# analog.net
KiCad netlist of a schematic drawn in Altium Designer
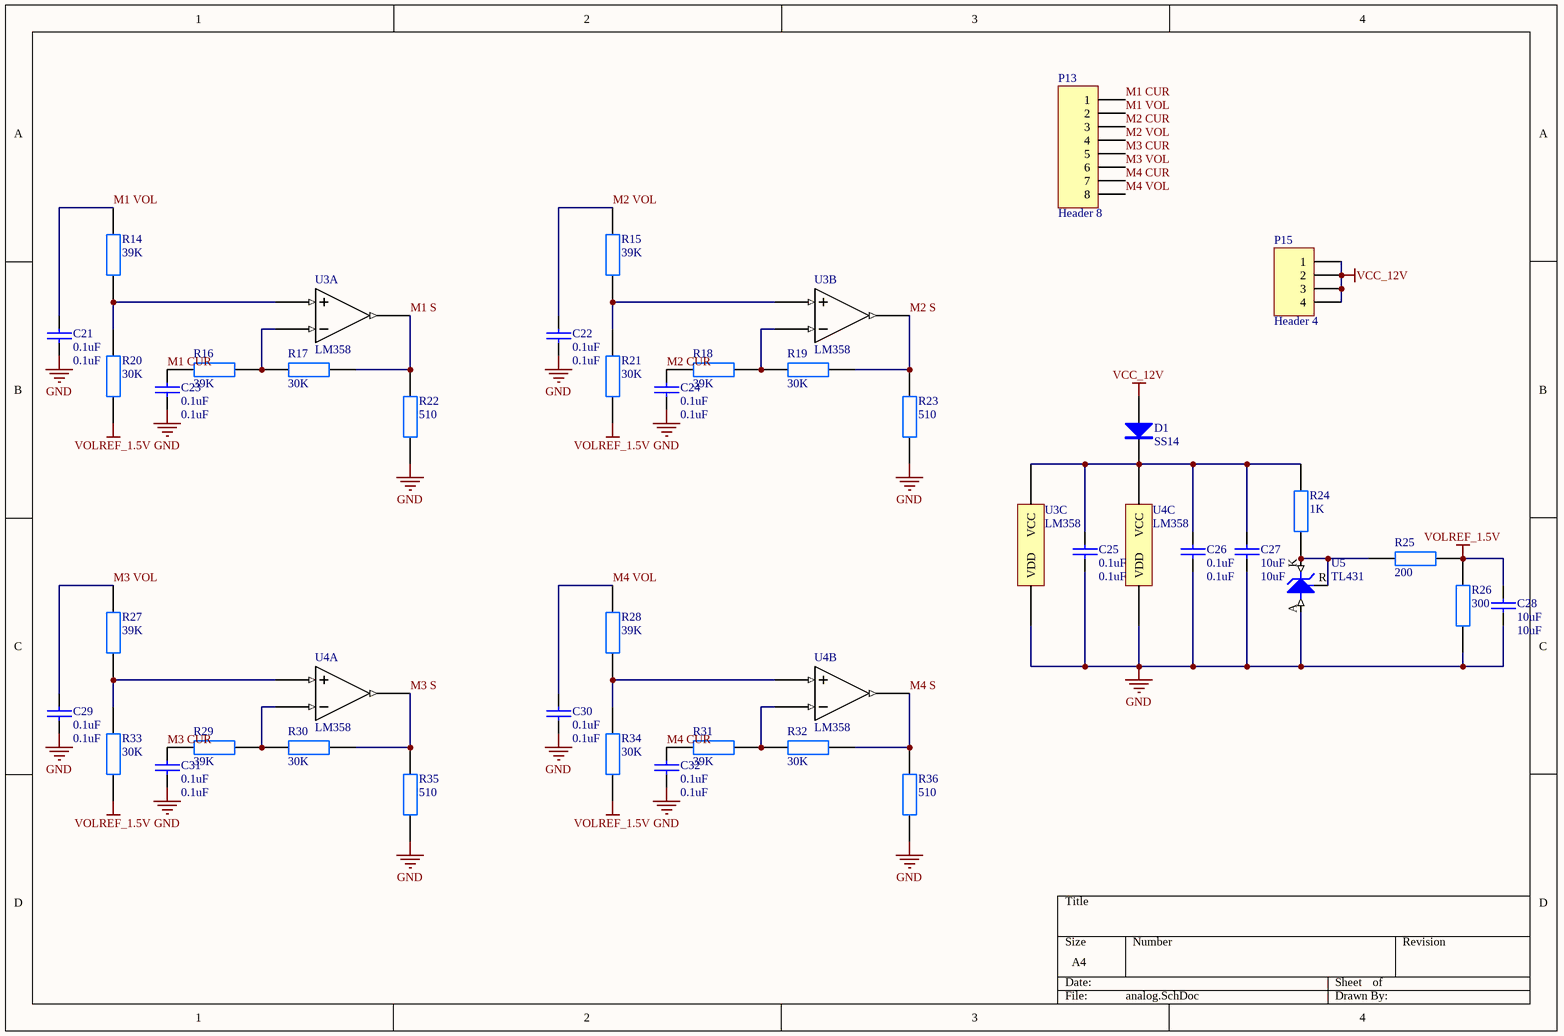
[diagram p0: analog.SchDoc]

(export (version "E")
  (design (tool "Eeschema 10.0.6"))
  (components
    (comp (ref "C21")
      (value "0.1uF")
      (footprint "0805 CAP")
      (fields (field (name "ALTIUM_VALUE") "0.1uF"))
      (libsource (lib "common") (part "CAP"))
    )
    (comp (ref "C22")
      (value "0.1uF")
      (footprint "0805 CAP")
      (fields (field (name "ALTIUM_VALUE") "0.1uF"))
      (libsource (lib "common") (part "CAP"))
    )
    (comp (ref "C23")
      (value "0.1uF")
      (footprint "0805 CAP")
      (fields (field (name "ALTIUM_VALUE") "0.1uF"))
      (libsource (lib "common") (part "CAP"))
    )
    (comp (ref "C24")
      (value "0.1uF")
      (footprint "0805 CAP")
      (fields (field (name "ALTIUM_VALUE") "0.1uF"))
      (libsource (lib "common") (part "CAP"))
    )
    (comp (ref "C25")
      (value "0.1uF")
      (footprint "0805 CAP")
      (fields (field (name "ALTIUM_VALUE") "0.1uF"))
      (libsource (lib "common") (part "CAP"))
    )
    (comp (ref "C26")
      (value "0.1uF")
      (footprint "0805 CAP")
      (fields (field (name "ALTIUM_VALUE") "0.1uF"))
      (libsource (lib "common") (part "CAP"))
    )
    (comp (ref "C27")
      (value "10uF")
      (footprint "0805 CAP")
      (fields (field (name "ALTIUM_VALUE") "10uF"))
      (libsource (lib "common") (part "CAP"))
    )
    (comp (ref "C28")
      (value "10uF")
      (footprint "0805 CAP")
      (fields (field (name "ALTIUM_VALUE") "10uF"))
      (libsource (lib "common") (part "CAP"))
    )
    (comp (ref "C29")
      (value "0.1uF")
      (footprint "0805 CAP")
      (fields (field (name "ALTIUM_VALUE") "0.1uF"))
      (libsource (lib "common") (part "CAP"))
    )
    (comp (ref "C30")
      (value "0.1uF")
      (footprint "0805 CAP")
      (fields (field (name "ALTIUM_VALUE") "0.1uF"))
      (libsource (lib "common") (part "CAP"))
    )
    (comp (ref "C31")
      (value "0.1uF")
      (footprint "0805 CAP")
      (fields (field (name "ALTIUM_VALUE") "0.1uF"))
      (libsource (lib "common") (part "CAP"))
    )
    (comp (ref "C32")
      (value "0.1uF")
      (footprint "0805 CAP")
      (fields (field (name "ALTIUM_VALUE") "0.1uF"))
      (libsource (lib "common") (part "CAP"))
    )
    (comp (ref "D1")
      (value "SS14")
      (footprint "DO-241AC")
      (description "Diode")
      (libsource (lib "common") (part "SS14"))
    )
    (comp (ref "P13")
      (value "Header 8")
      (footprint "sip8 i")
      (description "Header, 8-Pin")
      (fields (field (name "PUBLISHER") "Altium Limited"))
      (libsource (lib "Miscellaneous Connectors") (part "Header 8"))
    )
    (comp (ref "P15")
      (value "Header 4")
      (footprint "sip4 i")
      (description "Header, 4-Pin")
      (fields (field (name "PUBLISHER") "Altium Limited"))
      (libsource (lib "Miscellaneous Connectors") (part "Header 4"))
    )
    (comp (ref "R14")
      (value "39K")
      (footprint "0805")
      (description "RES")
      (libsource (lib "common") (part "RES"))
    )
    (comp (ref "R15")
      (value "39K")
      (footprint "0805")
      (description "RES")
      (libsource (lib "common") (part "RES"))
    )
    (comp (ref "R16")
      (value "39K")
      (footprint "0805")
      (description "RES")
      (libsource (lib "common") (part "RES"))
    )
    (comp (ref "R17")
      (value "30K")
      (footprint "0805")
      (description "RES")
      (libsource (lib "common") (part "RES"))
    )
    (comp (ref "R18")
      (value "39K")
      (footprint "0805")
      (description "RES")
      (libsource (lib "common") (part "RES"))
    )
    (comp (ref "R19")
      (value "30K")
      (footprint "0805")
      (description "RES")
      (libsource (lib "common") (part "RES"))
    )
    (comp (ref "R20")
      (value "30K")
      (footprint "0805")
      (description "RES")
      (libsource (lib "common") (part "RES"))
    )
    (comp (ref "R21")
      (value "30K")
      (footprint "0805")
      (description "RES")
      (libsource (lib "common") (part "RES"))
    )
    (comp (ref "R22")
      (value "510")
      (footprint "0805")
      (description "RES")
      (libsource (lib "common") (part "RES"))
    )
    (comp (ref "R23")
      (value "510")
      (footprint "0805")
      (description "RES")
      (libsource (lib "common") (part "RES"))
    )
    (comp (ref "R24")
      (value "1K")
      (footprint "0805")
      (description "RES")
      (libsource (lib "common") (part "RES"))
    )
    (comp (ref "R25")
      (value "200")
      (footprint "0805")
      (description "RES")
      (libsource (lib "common") (part "RES"))
    )
    (comp (ref "R26")
      (value "300")
      (footprint "0805")
      (description "RES")
      (libsource (lib "common") (part "RES"))
    )
    (comp (ref "R27")
      (value "39K")
      (footprint "0805")
      (description "RES")
      (libsource (lib "common") (part "RES"))
    )
    (comp (ref "R28")
      (value "39K")
      (footprint "0805")
      (description "RES")
      (libsource (lib "common") (part "RES"))
    )
    (comp (ref "R29")
      (value "39K")
      (footprint "0805")
      (description "RES")
      (libsource (lib "common") (part "RES"))
    )
    (comp (ref "R30")
      (value "30K")
      (footprint "0805")
      (description "RES")
      (libsource (lib "common") (part "RES"))
    )
    (comp (ref "R31")
      (value "39K")
      (footprint "0805")
      (description "RES")
      (libsource (lib "common") (part "RES"))
    )
    (comp (ref "R32")
      (value "30K")
      (footprint "0805")
      (description "RES")
      (libsource (lib "common") (part "RES"))
    )
    (comp (ref "R33")
      (value "30K")
      (footprint "0805")
      (description "RES")
      (libsource (lib "common") (part "RES"))
    )
    (comp (ref "R34")
      (value "30K")
      (footprint "0805")
      (description "RES")
      (libsource (lib "common") (part "RES"))
    )
    (comp (ref "R35")
      (value "510")
      (footprint "0805")
      (description "RES")
      (libsource (lib "common") (part "RES"))
    )
    (comp (ref "R36")
      (value "510")
      (footprint "0805")
      (description "RES")
      (libsource (lib "common") (part "RES"))
    )
    (comp (ref "U3") (value "LM358") (footprint "so-8") (libsource (lib "common") (part "LM358")))
    (comp (ref "U4") (value "LM358") (footprint "so-8") (libsource (lib "") (part "LM358_1")))
    (comp (ref "U5")
      (value "TL431")
      (footprint "sot-23")
      (description "IC")
      (libsource (lib "common") (part "TL431"))
    )
  )
  (nets
    (net (code "1") (name "/M1 CUR") (class "Default")
      (node (ref "C23") (pin "1") (pinfunction "1_1") (pintype "passive"))
      (node (ref "P13") (pin "1") (pinfunction "1_1") (pintype "passive"))
      (node (ref "R16") (pin "2") (pinfunction "2_2") (pintype "passive"))
    )
    (net (code "2") (name "/M1 S") (class "Default")
      (node (ref "R17") (pin "1") (pinfunction "1_1") (pintype "passive"))
      (node (ref "R22") (pin "2") (pinfunction "2_2") (pintype "passive"))
      (node (ref "U3") (pin "1") (pinfunction "1_1") (pintype "output"))
    )
    (net (code "3") (name "/M1 VOL") (class "Default")
      (node (ref "C21") (pin "1") (pinfunction "1_1") (pintype "passive"))
      (node (ref "P13") (pin "2") (pinfunction "2_2") (pintype "passive"))
      (node (ref "R14") (pin "2") (pinfunction "2_2") (pintype "passive"))
    )
    (net (code "4") (name "/M2 CUR") (class "Default")
      (node (ref "C24") (pin "1") (pinfunction "1_1") (pintype "passive"))
      (node (ref "P13") (pin "3") (pinfunction "3_3") (pintype "passive"))
      (node (ref "R18") (pin "2") (pinfunction "2_2") (pintype "passive"))
    )
    (net (code "5") (name "/M2 S") (class "Default")
      (node (ref "R19") (pin "1") (pinfunction "1_1") (pintype "passive"))
      (node (ref "R23") (pin "2") (pinfunction "2_2") (pintype "passive"))
      (node (ref "U3") (pin "7") (pinfunction "7_7") (pintype "output"))
    )
    (net (code "6") (name "/M2 VOL") (class "Default")
      (node (ref "C22") (pin "1") (pinfunction "1_1") (pintype "passive"))
      (node (ref "P13") (pin "4") (pinfunction "4_4") (pintype "passive"))
      (node (ref "R15") (pin "2") (pinfunction "2_2") (pintype "passive"))
    )
    (net (code "7") (name "/M3 CUR") (class "Default")
      (node (ref "C31") (pin "1") (pinfunction "1_1") (pintype "passive"))
      (node (ref "P13") (pin "5") (pinfunction "5_5") (pintype "passive"))
      (node (ref "R29") (pin "2") (pinfunction "2_2") (pintype "passive"))
    )
    (net (code "8") (name "/M3 S") (class "Default")
      (node (ref "R30") (pin "1") (pinfunction "1_1") (pintype "passive"))
      (node (ref "R35") (pin "2") (pinfunction "2_2") (pintype "passive"))
      (node (ref "U4") (pin "1") (pinfunction "1_1") (pintype "output"))
    )
    (net (code "9") (name "/M3 VOL") (class "Default")
      (node (ref "C29") (pin "1") (pinfunction "1_1") (pintype "passive"))
      (node (ref "P13") (pin "6") (pinfunction "6_6") (pintype "passive"))
      (node (ref "R27") (pin "2") (pinfunction "2_2") (pintype "passive"))
    )
    (net (code "10") (name "/M4 CUR") (class "Default")
      (node (ref "C32") (pin "1") (pinfunction "1_1") (pintype "passive"))
      (node (ref "P13") (pin "7") (pinfunction "7_7") (pintype "passive"))
      (node (ref "R31") (pin "2") (pinfunction "2_2") (pintype "passive"))
    )
    (net (code "11") (name "/M4 S") (class "Default")
      (node (ref "R32") (pin "1") (pinfunction "1_1") (pintype "passive"))
      (node (ref "R36") (pin "2") (pinfunction "2_2") (pintype "passive"))
      (node (ref "U4") (pin "7") (pinfunction "7_7") (pintype "output"))
    )
    (net (code "12") (name "/M4 VOL") (class "Default")
      (node (ref "C30") (pin "1") (pinfunction "1_1") (pintype "passive"))
      (node (ref "P13") (pin "8") (pinfunction "8_8") (pintype "passive"))
      (node (ref "R28") (pin "2") (pinfunction "2_2") (pintype "passive"))
    )
    (net (code "13") (name "GND") (class "Default")
      (node (ref "C21") (pin "2") (pinfunction "2_2") (pintype "passive"))
      (node (ref "C22") (pin "2") (pinfunction "2_2") (pintype "passive"))
      (node (ref "C23") (pin "2") (pinfunction "2_2") (pintype "passive"))
      (node (ref "C24") (pin "2") (pinfunction "2_2") (pintype "passive"))
      (node (ref "C25") (pin "2") (pinfunction "2_2") (pintype "passive"))
      (node (ref "C26") (pin "2") (pinfunction "2_2") (pintype "passive"))
      (node (ref "C27") (pin "2") (pinfunction "2_2") (pintype "passive"))
      (node (ref "C28") (pin "2") (pinfunction "2_2") (pintype "passive"))
      (node (ref "C29") (pin "2") (pinfunction "2_2") (pintype "passive"))
      (node (ref "C30") (pin "2") (pinfunction "2_2") (pintype "passive"))
      (node (ref "C31") (pin "2") (pinfunction "2_2") (pintype "passive"))
      (node (ref "C32") (pin "2") (pinfunction "2_2") (pintype "passive"))
      (node (ref "R22") (pin "1") (pinfunction "1_1") (pintype "passive"))
      (node (ref "R23") (pin "1") (pinfunction "1_1") (pintype "passive"))
      (node (ref "R26") (pin "1") (pinfunction "1_1") (pintype "passive"))
      (node (ref "R35") (pin "1") (pinfunction "1_1") (pintype "passive"))
      (node (ref "R36") (pin "1") (pinfunction "1_1") (pintype "passive"))
      (node (ref "U3") (pin "4") (pinfunction "VDD_4") (pintype "power_in"))
      (node (ref "U4") (pin "4") (pinfunction "VDD_4") (pintype "power_in"))
      (node (ref "U5") (pin "A") (pinfunction "A_A") (pintype "input"))
    )
    (net (code "14") (name "Net-(D1-K)") (class "Default")
      (node (ref "C25") (pin "1") (pinfunction "1_1") (pintype "passive"))
      (node (ref "C26") (pin "1") (pinfunction "1_1") (pintype "passive"))
      (node (ref "C27") (pin "1") (pinfunction "1_1") (pintype "passive"))
      (node (ref "D1") (pin "2") (pinfunction "K_2") (pintype "passive"))
      (node (ref "R24") (pin "2") (pinfunction "2_2") (pintype "passive"))
      (node (ref "U3") (pin "8") (pinfunction "VCC_8") (pintype "power_in"))
      (node (ref "U4") (pin "8") (pinfunction "VCC_8") (pintype "power_in"))
    )
    (net (code "15") (name "Net-(R14-Pad1)") (class "Default")
      (node (ref "R14") (pin "1") (pinfunction "1_1") (pintype "passive"))
      (node (ref "R20") (pin "2") (pinfunction "2_2") (pintype "passive"))
      (node (ref "U3") (pin "3") (pinfunction "3_3") (pintype "input"))
    )
    (net (code "16") (name "Net-(R15-Pad1)") (class "Default")
      (node (ref "R15") (pin "1") (pinfunction "1_1") (pintype "passive"))
      (node (ref "R21") (pin "2") (pinfunction "2_2") (pintype "passive"))
      (node (ref "U3") (pin "5") (pinfunction "5_5") (pintype "input"))
    )
    (net (code "17") (name "Net-(R16-Pad1)") (class "Default")
      (node (ref "R16") (pin "1") (pinfunction "1_1") (pintype "passive"))
      (node (ref "R17") (pin "2") (pinfunction "2_2") (pintype "passive"))
      (node (ref "U3") (pin "2") (pinfunction "2_2") (pintype "input"))
    )
    (net (code "18") (name "Net-(R18-Pad1)") (class "Default")
      (node (ref "R18") (pin "1") (pinfunction "1_1") (pintype "passive"))
      (node (ref "R19") (pin "2") (pinfunction "2_2") (pintype "passive"))
      (node (ref "U3") (pin "6") (pinfunction "6_6") (pintype "input"))
    )
    (net (code "19") (name "Net-(R24-Pad1)") (class "Default")
      (node (ref "R24") (pin "1") (pinfunction "1_1") (pintype "passive"))
      (node (ref "R25") (pin "2") (pinfunction "2_2") (pintype "passive"))
      (node (ref "U5") (pin "K") (pinfunction "K_K") (pintype "input"))
      (node (ref "U5") (pin "R") (pinfunction "R_R") (pintype "passive"))
    )
    (net (code "20") (name "Net-(R27-Pad1)") (class "Default")
      (node (ref "R27") (pin "1") (pinfunction "1_1") (pintype "passive"))
      (node (ref "R33") (pin "2") (pinfunction "2_2") (pintype "passive"))
      (node (ref "U4") (pin "3") (pinfunction "3_3") (pintype "input"))
    )
    (net (code "21") (name "Net-(R28-Pad1)") (class "Default")
      (node (ref "R28") (pin "1") (pinfunction "1_1") (pintype "passive"))
      (node (ref "R34") (pin "2") (pinfunction "2_2") (pintype "passive"))
      (node (ref "U4") (pin "5") (pinfunction "5_5") (pintype "input"))
    )
    (net (code "22") (name "Net-(R29-Pad1)") (class "Default")
      (node (ref "R29") (pin "1") (pinfunction "1_1") (pintype "passive"))
      (node (ref "R30") (pin "2") (pinfunction "2_2") (pintype "passive"))
      (node (ref "U4") (pin "2") (pinfunction "2_2") (pintype "input"))
    )
    (net (code "23") (name "Net-(R31-Pad1)") (class "Default")
      (node (ref "R31") (pin "1") (pinfunction "1_1") (pintype "passive"))
      (node (ref "R32") (pin "2") (pinfunction "2_2") (pintype "passive"))
      (node (ref "U4") (pin "6") (pinfunction "6_6") (pintype "input"))
    )
    (net (code "24") (name "VCC_12V") (class "Default")
      (node (ref "D1") (pin "1") (pinfunction "A_1") (pintype "passive"))
      (node (ref "P15") (pin "1") (pinfunction "1_1") (pintype "passive"))
      (node (ref "P15") (pin "2") (pinfunction "2_2") (pintype "passive"))
      (node (ref "P15") (pin "3") (pinfunction "3_3") (pintype "passive"))
      (node (ref "P15") (pin "4") (pinfunction "4_4") (pintype "passive"))
    )
    (net (code "25") (name "VOLREF_1.5V") (class "Default")
      (node (ref "C28") (pin "1") (pinfunction "1_1") (pintype "passive"))
      (node (ref "R20") (pin "1") (pinfunction "1_1") (pintype "passive"))
      (node (ref "R21") (pin "1") (pinfunction "1_1") (pintype "passive"))
      (node (ref "R25") (pin "1") (pinfunction "1_1") (pintype "passive"))
      (node (ref "R26") (pin "2") (pinfunction "2_2") (pintype "passive"))
      (node (ref "R33") (pin "1") (pinfunction "1_1") (pintype "passive"))
      (node (ref "R34") (pin "1") (pinfunction "1_1") (pintype "passive"))
    )
  )
)
